# Power_Supply.net
KiCad netlist of a schematic drawn in Altium Designer
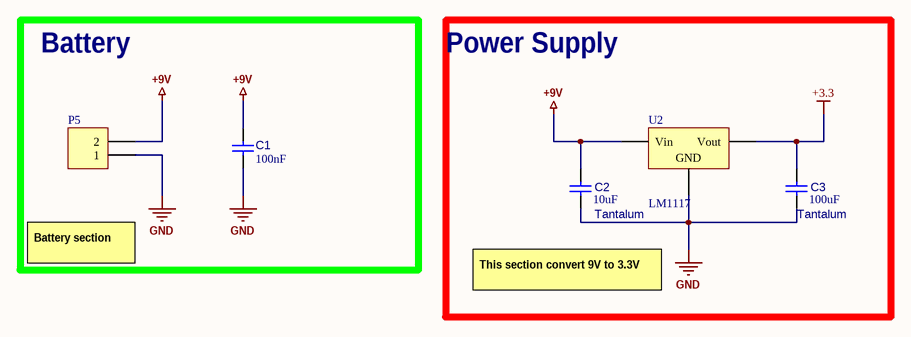
[diagram p0: Power_Supply.SchDoc]

(export (version "E")
  (design (tool "Eeschema 10.0.6"))
  (components
    (comp (ref "C1")
      (value "100nF")
      (footprint "CAPC2013X95X50LL10T25")
      (description "Chip Capacitor, 100 nF, +/- 10%, 50 V, 0805 (2012 Metric)")
      (fields (field (name "TOLERANCE") "10%") (field (name "Comment") "Capacitor 100 nF +/-10% 50 V 0805"))
      (libsource (lib "Averna Test Systems") (part "CAP-NP-2"))
    )
    (comp (ref "C2")
      (value "Tantalum")
      (footprint "CAPC2013X95X50LL10T25")
      (description "Chip Capacitor, 100 nF, +/- 10%, 50 V, 0805 (2012 Metric)")
      (fields (field (name "ALTIUM_VALUE") "10uF") (field (name "TOLERANCE") "10%"))
      (libsource (lib "Averna Test Systems") (part "CAP-NP-2"))
    )
    (comp (ref "C3")
      (value "Tantalum")
      (footprint "CAPC2013X95X50LL10T25")
      (description "Chip Capacitor, 100 nF, +/- 10%, 50 V, 0805 (2012 Metric)")
      (fields (field (name "ALTIUM_VALUE") "100uF") (field (name "TOLERANCE") "10%"))
      (libsource (lib "Averna Test Systems") (part "CAP-NP-2"))
    )
    (comp (ref "P5")
      (value "Battery connection")
      (footprint "PHOE-1803277_V")
      (description "Header, 2-Pin")
      (fields (field (name "ASID PART NUMBER") "Header 2-AS"))
      (libsource (lib "Mylib_Rev_4") (part "Header 2"))
    )
    (comp (ref "U2")
      (value "LM1117")
      (footprint "MY_SOT223")
      (description "Low Drop Voltage Reg")
      (fields (field (name "ASID PART NUMBER") "LM1117-AS"))
      (libsource (lib "Mylib_Rev_4") (part "LM1117"))
    )
  )
  (nets
    (net (code "1") (name "+3.3") (class "Default")
      (node (ref "C3") (pin "1") (pinfunction "1_1") (pintype "passive"))
      (node (ref "U2") (pin "2") (pinfunction "Vout_2") (pintype "passive"))
    )
    (net (code "2") (name "+9V") (class "Default")
      (node (ref "C1") (pin "1") (pinfunction "1_1") (pintype "passive"))
      (node (ref "C2") (pin "1") (pinfunction "1_1") (pintype "passive"))
      (node (ref "P5") (pin "2") (pinfunction "2_2") (pintype "passive"))
      (node (ref "U2") (pin "3") (pinfunction "Vin_3") (pintype "passive"))
    )
    (net (code "3") (name "GND") (class "Default")
      (node (ref "C1") (pin "2") (pinfunction "2_2") (pintype "passive"))
      (node (ref "C2") (pin "2") (pinfunction "2_2") (pintype "passive"))
      (node (ref "C3") (pin "2") (pinfunction "2_2") (pintype "passive"))
      (node (ref "P5") (pin "1") (pinfunction "1_1") (pintype "passive"))
      (node (ref "U2") (pin "1") (pinfunction "GND_1") (pintype "passive"))
    )
  )
)
